# quadstick1.net
KiCad netlist of a schematic drawn in EAGLE
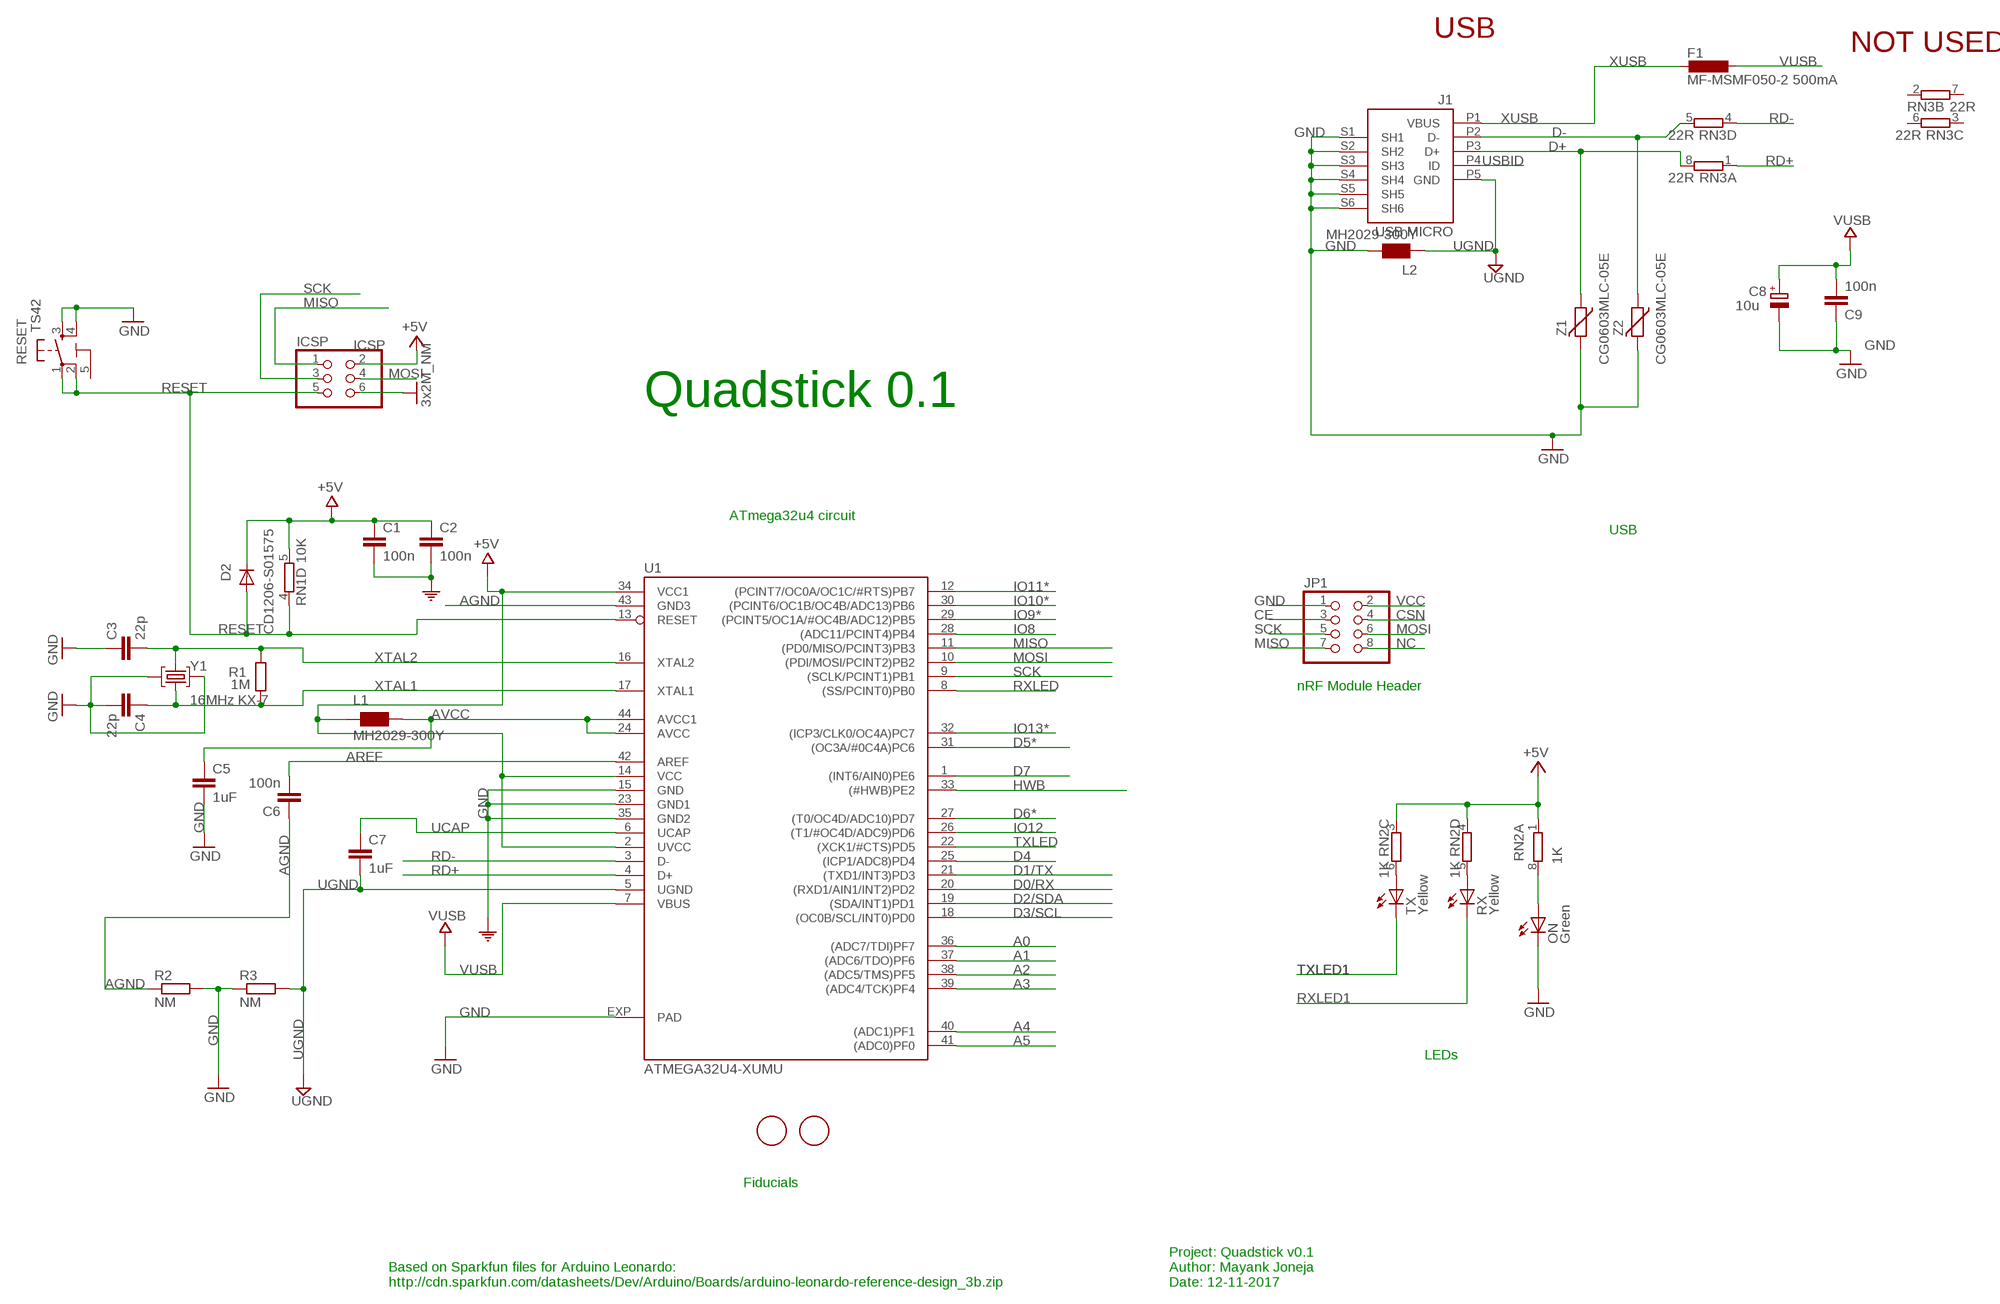
[diagram p0: schematic, sheet 1]

(export (version "E")
  (design (tool "Eeschema 10.0.6"))
  (components
    (comp (ref "C1")
      (value "100n")
      (footprint "eagle-import:C0603-ROUND")
      (libsource (lib "eagle-import") (part "C-EUC0603"))
    )
    (comp (ref "C2")
      (value "100n")
      (footprint "eagle-import:C0603-ROUND")
      (libsource (lib "eagle-import") (part "C-EUC0603"))
    )
    (comp (ref "C3")
      (value "22p")
      (footprint "eagle-import:C0603-ROUND")
      (libsource (lib "eagle-import") (part "C-EUC0603"))
    )
    (comp (ref "C4")
      (value "22p")
      (footprint "eagle-import:C0603-ROUND")
      (libsource (lib "eagle-import") (part "C-EUC0603"))
    )
    (comp (ref "C5")
      (value "1uF")
      (footprint "eagle-import:C0603-ROUND")
      (libsource (lib "eagle-import") (part "C-EUC0603"))
    )
    (comp (ref "C6")
      (value "100n")
      (footprint "eagle-import:C0603-ROUND")
      (libsource (lib "eagle-import") (part "C-EUC0603"))
    )
    (comp (ref "C7")
      (value "1uF")
      (footprint "eagle-import:C0603-ROUND")
      (libsource (lib "eagle-import") (part "C-EUC0603"))
    )
    (comp (ref "C8")
      (value "10u")
      (footprint "eagle-import:SMC_B")
      (libsource (lib "eagle-import") (part "CPOL-EUSMCB"))
    )
    (comp (ref "C9")
      (value "100n")
      (footprint "eagle-import:C0603-ROUND")
      (libsource (lib "eagle-import") (part "C-EUC0603"))
    )
    (comp (ref "D2")
      (value "CD1206-S01575")
      (footprint "eagle-import:MINIMELF")
      (libsource (lib "eagle-import") (part "DIODE-MINIMELF"))
    )
    (comp (ref "F1")
      (value "MF-MSMF050-2 500mA")
      (footprint "eagle-import:L1812")
      (libsource (lib "eagle-import") (part "L-EUL1812"))
    )
    (comp (ref "FID2")
      (value "FIDUCIALMOUNT")
      (footprint "eagle-import:FIDUCIA-MOUNT")
      (libsource (lib "eagle-import") (part "FIDUCIALMOUNT"))
    )
    (comp (ref "FID3")
      (value "FIDUCIALMOUNT")
      (footprint "eagle-import:FIDUCIA-MOUNT")
      (libsource (lib "eagle-import") (part "FIDUCIALMOUNT"))
    )
    (comp (ref "ICSP")
      (value "ICSP")
      (footprint "eagle-import:2X03")
      (libsource (lib "eagle-import") (part "PINHD-2X3"))
    )
    (comp (ref "J1")
      (value "USB MICRO")
      (footprint "eagle-import:CON2_USB_MICRO_B_AT")
      (libsource (lib "eagle-import") (part "MYCON2_USB-MINI-B"))
    )
    (comp (ref "JP1")
      (value "PINHD-2X4")
      (footprint "eagle-import:2X04")
      (libsource (lib "eagle-import") (part "PINHD-2X4"))
    )
    (comp (ref "L1")
      (value "MH2029-300Y")
      (footprint "eagle-import:0805")
      (libsource (lib "eagle-import") (part "WE-CBF_0805"))
    )
    (comp (ref "L2")
      (value "MH2029-300Y")
      (footprint "eagle-import:0805")
      (libsource (lib "eagle-import") (part "WE-CBF_0805"))
    )
    (comp (ref "ON")
      (value "Green")
      (footprint "eagle-import:CHIPLED_0805")
      (libsource (lib "eagle-import") (part "LEDCHIPLED_0805"))
    )
    (comp (ref "R1")
      (value "1M")
      (footprint "eagle-import:R0603-ROUND")
      (libsource (lib "eagle-import") (part "R-EU_R0603"))
    )
    (comp (ref "R2")
      (value "NM")
      (footprint "eagle-import:R0402")
      (libsource (lib "eagle-import") (part "R-EU_R0402"))
    )
    (comp (ref "R3")
      (value "NM")
      (footprint "eagle-import:R0402")
      (libsource (lib "eagle-import") (part "R-EU_R0402"))
    )
    (comp (ref "RESET")
      (value "TS42")
      (footprint "eagle-import:TS42")
      (libsource (lib "eagle-import") (part "TS42"))
    )
    (comp (ref "RN1")
      (value "10K")
      (footprint "eagle-import:CAY16")
      (libsource (lib "eagle-import") (part "4R-NCAY16"))
    )
    (comp (ref "RN2")
      (value "1K")
      (footprint "eagle-import:CAY16")
      (libsource (lib "eagle-import") (part "4R-NCAY16"))
    )
    (comp (ref "RN3")
      (value "22R")
      (footprint "eagle-import:CAY16")
      (libsource (lib "eagle-import") (part "4R-NCAY16"))
    )
    (comp (ref "RX")
      (value "Yellow")
      (footprint "eagle-import:CHIPLED_0805")
      (libsource (lib "eagle-import") (part "LEDCHIPLED_0805"))
    )
    (comp (ref "TX")
      (value "Yellow")
      (footprint "eagle-import:CHIPLED_0805")
      (libsource (lib "eagle-import") (part "LEDCHIPLED_0805"))
    )
    (comp (ref "U1")
      (value "ATMEGA32U4-XUMU")
      (footprint "eagle-import:QFN44ML7X7")
      (libsource (lib "eagle-import") (part "ATMEGA32U4-XUMU"))
    )
    (comp (ref "Y1")
      (value "16MHz KX-7")
      (footprint "eagle-import:CRYSTAL-3.2-2.5")
      (libsource (lib "eagle-import") (part "CRYSTAL-3.2-2.5"))
    )
    (comp (ref "Z1")
      (value "CG0603MLC-05E")
      (footprint "eagle-import:CT_CN0603")
      (libsource (lib "eagle-import") (part "VARISTORCN0603"))
    )
    (comp (ref "Z2")
      (value "CG0603MLC-05E")
      (footprint "eagle-import:CT_CN0603")
      (libsource (lib "eagle-import") (part "VARISTORCN0603"))
    )
  )
  (nets
    (net (code "1") (name "+5V") (class "Default")
      (node (ref "C1") (pin "1") (pinfunction "1_1") (pintype "passive"))
      (node (ref "C2") (pin "1") (pinfunction "1_1") (pintype "passive"))
      (node (ref "D2") (pin "C") (pinfunction "C_C") (pintype "passive"))
      (node (ref "ICSP") (pin "2") (pinfunction "2_2") (pintype "passive"))
      (node (ref "L1") (pin "1") (pinfunction "1_1") (pintype "passive"))
      (node (ref "RN1") (pin "5") (pinfunction "2_5") (pintype "passive"))
      (node (ref "RN2") (pin "1") (pinfunction "1_1") (pintype "passive"))
      (node (ref "RN2") (pin "3") (pinfunction "1_3") (pintype "passive"))
      (node (ref "RN2") (pin "4") (pinfunction "1_4") (pintype "passive"))
      (node (ref "U1") (pin "14") (pinfunction "VCC_14") (pintype "power_in"))
      (node (ref "U1") (pin "2") (pinfunction "UVCC_2") (pintype "power_in"))
      (node (ref "U1") (pin "34") (pinfunction "VCC1_34") (pintype "power_in"))
    )
    (net (code "2") (name "/5-GND") (class "Default")
      (node (ref "RESET") (pin "5") (pinfunction "5-GND_5") (pintype "power_in"))
    )
    (net (code "3") (name "/A0") (class "Default")
      (node (ref "U1") (pin "36") (pinfunction "(ADC7/TDI)PF7_36") (pintype "bidirectional"))
    )
    (net (code "4") (name "/A1") (class "Default")
      (node (ref "U1") (pin "37") (pinfunction "(ADC6/TDO)PF6_37") (pintype "bidirectional"))
    )
    (net (code "5") (name "/A2") (class "Default")
      (node (ref "U1") (pin "38") (pinfunction "(ADC5/TMS)PF5_38") (pintype "bidirectional"))
    )
    (net (code "6") (name "/A3") (class "Default")
      (node (ref "U1") (pin "39") (pinfunction "(ADC4/TCK)PF4_39") (pintype "bidirectional"))
    )
    (net (code "7") (name "/A4") (class "Default")
      (node (ref "U1") (pin "40") (pinfunction "(ADC1)PF1_40") (pintype "bidirectional"))
    )
    (net (code "8") (name "/A5") (class "Default")
      (node (ref "U1") (pin "41") (pinfunction "(ADC0)PF0_41") (pintype "bidirectional"))
    )
    (net (code "9") (name "/AGND") (class "Default")
      (node (ref "C6") (pin "1") (pinfunction "1_1") (pintype "passive"))
      (node (ref "R2") (pin "1") (pinfunction "1_1") (pintype "passive"))
      (node (ref "U1") (pin "43") (pinfunction "GND3_43") (pintype "power_in"))
    )
    (net (code "10") (name "/AREF") (class "Default")
      (node (ref "C6") (pin "2") (pinfunction "2_2") (pintype "passive"))
      (node (ref "U1") (pin "42") (pinfunction "AREF_42") (pintype "power_in"))
    )
    (net (code "11") (name "/AVCC") (class "Default")
      (node (ref "C5") (pin "1") (pinfunction "1_1") (pintype "passive"))
      (node (ref "L1") (pin "2") (pinfunction "2_2") (pintype "passive"))
      (node (ref "U1") (pin "24") (pinfunction "AVCC_24") (pintype "power_in"))
      (node (ref "U1") (pin "44") (pinfunction "AVCC1_44") (pintype "power_in"))
    )
    (net (code "12") (name "/CE") (class "Default")
      (node (ref "JP1") (pin "3") (pinfunction "3_3") (pintype "passive"))
    )
    (net (code "13") (name "/CSN") (class "Default")
      (node (ref "JP1") (pin "4") (pinfunction "4_4") (pintype "passive"))
    )
    (net (code "14") (name "/D+") (class "Default")
      (node (ref "J1") (pin "P3") (pinfunction "D+_P3") (pintype "bidirectional"))
      (node (ref "RN3") (pin "8") (pinfunction "2_8") (pintype "passive"))
      (node (ref "Z1") (pin "1") (pinfunction "1_1") (pintype "passive"))
    )
    (net (code "15") (name "/D-") (class "Default")
      (node (ref "J1") (pin "P2") (pinfunction "D-_P2") (pintype "bidirectional"))
      (node (ref "RN3") (pin "5") (pinfunction "2_5") (pintype "passive"))
      (node (ref "Z2") (pin "1") (pinfunction "1_1") (pintype "passive"))
    )
    (net (code "16") (name "/D0{slash}RX") (class "Default")
      (node (ref "U1") (pin "20") (pinfunction "(RXD1/AIN1/INT2)PD2_20") (pintype "bidirectional"))
    )
    (net (code "17") (name "/D1{slash}TX") (class "Default")
      (node (ref "U1") (pin "21") (pinfunction "(TXD1/INT3)PD3_21") (pintype "bidirectional"))
    )
    (net (code "18") (name "/D2{slash}SDA") (class "Default")
      (node (ref "U1") (pin "19") (pinfunction "(SDA/INT1)PD1_19") (pintype "bidirectional"))
    )
    (net (code "19") (name "/D3{slash}SCL") (class "Default")
      (node (ref "U1") (pin "18") (pinfunction "(OC0B/SCL/INT0)PD0_18") (pintype "bidirectional"))
    )
    (net (code "20") (name "/D4") (class "Default")
      (node (ref "U1") (pin "25") (pinfunction "(ICP1/ADC8)PD4_25") (pintype "bidirectional"))
    )
    (net (code "21") (name "/D5*") (class "Default")
      (node (ref "U1") (pin "31") (pinfunction "(OC3A/#0C4A)PC6_31") (pintype "bidirectional"))
    )
    (net (code "22") (name "/D6*") (class "Default")
      (node (ref "U1") (pin "27") (pinfunction "(T0/OC4D/ADC10)PD7_27") (pintype "bidirectional"))
    )
    (net (code "23") (name "/D7") (class "Default")
      (node (ref "U1") (pin "1") (pinfunction "(INT6/AIN0)PE6_1") (pintype "bidirectional"))
    )
    (net (code "24") (name "/HWB") (class "Default")
      (node (ref "U1") (pin "33") (pinfunction "(#HWB)PE2_33") (pintype "bidirectional"))
    )
    (net (code "25") (name "/IO8") (class "Default")
      (node (ref "U1") (pin "28") (pinfunction "(ADC11/PCINT4)PB4_28") (pintype "bidirectional"))
    )
    (net (code "26") (name "/IO9*") (class "Default")
      (node (ref "U1") (pin "29") (pinfunction "(PCINT5/OC1A/#OC4B/ADC12)PB5_29") (pintype "bidirectional"))
    )
    (net (code "27") (name "/IO10*") (class "Default")
      (node (ref "U1") (pin "30") (pinfunction "(PCINT6/OC1B/OC4B/ADC13)PB6_30") (pintype "bidirectional"))
    )
    (net (code "28") (name "/IO11*") (class "Default")
      (node (ref "U1") (pin "12") (pinfunction "(PCINT7/OC0A/OC1C/#RTS)PB7_12") (pintype "bidirectional"))
    )
    (net (code "29") (name "/IO12") (class "Default")
      (node (ref "U1") (pin "26") (pinfunction "(T1/#OC4D/ADC9)PD6_26") (pintype "bidirectional"))
    )
    (net (code "30") (name "/IO13*") (class "Default")
      (node (ref "U1") (pin "32") (pinfunction "(ICP3/CLK0/OC4A)PC7_32") (pintype "bidirectional"))
    )
    (net (code "31") (name "/MISO") (class "Default")
      (node (ref "ICSP") (pin "1") (pinfunction "1_1") (pintype "passive"))
      (node (ref "JP1") (pin "7") (pinfunction "7_7") (pintype "passive"))
      (node (ref "U1") (pin "11") (pinfunction "(PD0/MISO/PCINT3)PB3_11") (pintype "bidirectional"))
    )
    (net (code "32") (name "/MOSI") (class "Default")
      (node (ref "ICSP") (pin "4") (pinfunction "4_4") (pintype "passive"))
      (node (ref "JP1") (pin "6") (pinfunction "6_6") (pintype "passive"))
      (node (ref "U1") (pin "10") (pinfunction "(PDI/MOSI/PCINT2)PB2_10") (pintype "bidirectional"))
    )
    (net (code "33") (name "/NC") (class "Default")
      (node (ref "JP1") (pin "8") (pinfunction "8_8") (pintype "passive"))
    )
    (net (code "34") (name "/RD+") (class "Default")
      (node (ref "RN3") (pin "1") (pinfunction "1_1") (pintype "passive"))
      (node (ref "U1") (pin "4") (pinfunction "D+_4") (pintype "bidirectional"))
    )
    (net (code "35") (name "/RD-") (class "Default")
      (node (ref "RN3") (pin "4") (pinfunction "1_4") (pintype "passive"))
      (node (ref "U1") (pin "3") (pinfunction "D-_3") (pintype "bidirectional"))
    )
    (net (code "36") (name "/RESET") (class "Default")
      (node (ref "D2") (pin "A") (pinfunction "A_A") (pintype "passive"))
      (node (ref "ICSP") (pin "5") (pinfunction "5_5") (pintype "passive"))
      (node (ref "RESET") (pin "1") (pinfunction "1_1") (pintype "passive"))
      (node (ref "RESET") (pin "2") (pinfunction "2_2") (pintype "passive"))
      (node (ref "RN1") (pin "4") (pinfunction "1_4") (pintype "passive"))
      (node (ref "U1") (pin "13") (pinfunction "RESET_13") (pintype "input"))
    )
    (net (code "37") (name "/RXLED") (class "Default")
      (node (ref "U1") (pin "8") (pinfunction "(SS/PCINT0)PB0_8") (pintype "bidirectional"))
    )
    (net (code "38") (name "/RXLED1") (class "Default")
      (node (ref "RX") (pin "C") (pinfunction "C_C") (pintype "passive"))
    )
    (net (code "39") (name "/SCK") (class "Default")
      (node (ref "ICSP") (pin "3") (pinfunction "3_3") (pintype "passive"))
      (node (ref "JP1") (pin "5") (pinfunction "5_5") (pintype "passive"))
      (node (ref "U1") (pin "9") (pinfunction "(SCLK/PCINT1)PB1_9") (pintype "bidirectional"))
    )
    (net (code "40") (name "/TXLED") (class "Default")
      (node (ref "U1") (pin "22") (pinfunction "(XCK1/#CTS)PD5_22") (pintype "bidirectional"))
    )
    (net (code "41") (name "/TXLED1") (class "Default")
      (node (ref "TX") (pin "C") (pinfunction "C_C") (pintype "passive"))
    )
    (net (code "42") (name "/UCAP") (class "Default")
      (node (ref "C7") (pin "1") (pinfunction "1_1") (pintype "passive"))
      (node (ref "U1") (pin "6") (pinfunction "UCAP_6") (pintype "passive"))
    )
    (net (code "43") (name "/USBID") (class "Default")
      (node (ref "J1") (pin "P4") (pinfunction "ID_P4") (pintype "bidirectional"))
    )
    (net (code "44") (name "/VCC") (class "Default")
      (node (ref "JP1") (pin "2") (pinfunction "2_2") (pintype "passive"))
    )
    (net (code "45") (name "/XTAL1") (class "Default")
      (node (ref "C4") (pin "1") (pinfunction "1_1") (pintype "passive"))
      (node (ref "R1") (pin "1") (pinfunction "1_1") (pintype "passive"))
      (node (ref "U1") (pin "17") (pinfunction "XTAL1_17") (pintype "bidirectional"))
      (node (ref "Y1") (pin "1") (pinfunction "C1_1") (pintype "passive"))
    )
    (net (code "46") (name "/XTAL2") (class "Default")
      (node (ref "C3") (pin "2") (pinfunction "2_2") (pintype "passive"))
      (node (ref "R1") (pin "2") (pinfunction "2_2") (pintype "passive"))
      (node (ref "U1") (pin "16") (pinfunction "XTAL2_16") (pintype "bidirectional"))
      (node (ref "Y1") (pin "3") (pinfunction "C2_3") (pintype "passive"))
    )
    (net (code "47") (name "/XUSB") (class "Default")
      (node (ref "F1") (pin "2") (pinfunction "2_2") (pintype "passive"))
      (node (ref "J1") (pin "P1") (pinfunction "VBUS_P1") (pintype "power_in"))
    )
    (net (code "48") (name "3x2M_NM") (class "Default")
      (node (ref "C1") (pin "2") (pinfunction "2_2") (pintype "passive"))
      (node (ref "C2") (pin "2") (pinfunction "2_2") (pintype "passive"))
      (node (ref "C3") (pin "1") (pinfunction "1_1") (pintype "passive"))
      (node (ref "C4") (pin "2") (pinfunction "2_2") (pintype "passive"))
      (node (ref "C5") (pin "2") (pinfunction "2_2") (pintype "passive"))
      (node (ref "C8") (pin "-") (pinfunction "-_-") (pintype "passive"))
      (node (ref "C9") (pin "1") (pinfunction "1_1") (pintype "passive"))
      (node (ref "ICSP") (pin "6") (pinfunction "6_6") (pintype "passive"))
      (node (ref "J1") (pin "S1") (pinfunction "SH1_S1") (pintype "passive"))
      (node (ref "J1") (pin "S2") (pinfunction "SH2_S2") (pintype "passive"))
      (node (ref "J1") (pin "S3") (pinfunction "SH3_S3") (pintype "passive"))
      (node (ref "J1") (pin "S4") (pinfunction "SH4_S4") (pintype "passive"))
      (node (ref "J1") (pin "S5") (pinfunction "SH5_S5") (pintype "passive"))
      (node (ref "J1") (pin "S6") (pinfunction "SH6_S6") (pintype "passive"))
      (node (ref "JP1") (pin "1") (pinfunction "1_1") (pintype "passive"))
      (node (ref "L2") (pin "2") (pinfunction "2_2") (pintype "passive"))
      (node (ref "ON") (pin "C") (pinfunction "C_C") (pintype "passive"))
      (node (ref "R2") (pin "2") (pinfunction "2_2") (pintype "passive"))
      (node (ref "R3") (pin "1") (pinfunction "1_1") (pintype "passive"))
      (node (ref "RESET") (pin "3") (pinfunction "3_3") (pintype "passive"))
      (node (ref "RESET") (pin "4") (pinfunction "4_4") (pintype "passive"))
      (node (ref "U1") (pin "15") (pinfunction "GND_15") (pintype "power_in"))
      (node (ref "U1") (pin "23") (pinfunction "GND1_23") (pintype "power_in"))
      (node (ref "U1") (pin "35") (pinfunction "GND2_35") (pintype "power_in"))
      (node (ref "U1") (pin "EXP") (pinfunction "PAD_EXP") (pintype "power_in"))
      (node (ref "Y1") (pin "2") (pinfunction "GND_2") (pintype "passive"))
      (node (ref "Y1") (pin "4") (pinfunction "GND_4") (pintype "passive"))
      (node (ref "Z1") (pin "2") (pinfunction "2_2") (pintype "passive"))
      (node (ref "Z2") (pin "2") (pinfunction "2_2") (pintype "passive"))
    )
    (net (code "49") (name "Net-(RN2A-2)") (class "Default")
      (node (ref "ON") (pin "A") (pinfunction "A_A") (pintype "passive"))
      (node (ref "RN2") (pin "8") (pinfunction "2_8") (pintype "passive"))
    )
    (net (code "50") (name "Net-(RN2C-2)") (class "Default")
      (node (ref "RN2") (pin "6") (pinfunction "2_6") (pintype "passive"))
      (node (ref "TX") (pin "A") (pinfunction "A_A") (pintype "passive"))
    )
    (net (code "51") (name "Net-(RN2D-2)") (class "Default")
      (node (ref "RN2") (pin "5") (pinfunction "2_5") (pintype "passive"))
      (node (ref "RX") (pin "A") (pinfunction "A_A") (pintype "passive"))
    )
    (net (code "52") (name "UGND") (class "Default")
      (node (ref "C7") (pin "2") (pinfunction "2_2") (pintype "passive"))
      (node (ref "J1") (pin "P5") (pinfunction "GND_P5") (pintype "passive"))
      (node (ref "L2") (pin "1") (pinfunction "1_1") (pintype "passive"))
      (node (ref "R3") (pin "2") (pinfunction "2_2") (pintype "passive"))
      (node (ref "U1") (pin "5") (pinfunction "UGND_5") (pintype "power_in"))
    )
    (net (code "53") (name "VUSB") (class "Default")
      (node (ref "C8") (pin "+") (pinfunction "+_+") (pintype "passive"))
      (node (ref "C9") (pin "2") (pinfunction "2_2") (pintype "passive"))
      (node (ref "F1") (pin "1") (pinfunction "1_1") (pintype "passive"))
      (node (ref "U1") (pin "7") (pinfunction "VBUS_7") (pintype "input"))
    )
    (net (code "54") (name "unconnected-(RN3B-1-Pad2)") (class "Default")
      (node (ref "RN3") (pin "2") (pinfunction "1_2") (pintype "passive"))
    )
    (net (code "55") (name "unconnected-(RN3B-2-Pad7)") (class "Default")
      (node (ref "RN3") (pin "7") (pinfunction "2_7") (pintype "passive"))
    )
    (net (code "56") (name "unconnected-(RN3C-1-Pad3)") (class "Default")
      (node (ref "RN3") (pin "3") (pinfunction "1_3") (pintype "passive"))
    )
    (net (code "57") (name "unconnected-(RN3C-2-Pad6)") (class "Default")
      (node (ref "RN3") (pin "6") (pinfunction "2_6") (pintype "passive"))
    )
  )
)
